# 06_MIMXRT1170_PART2.net
KiCad netlist of a schematic drawn in Altium Designer
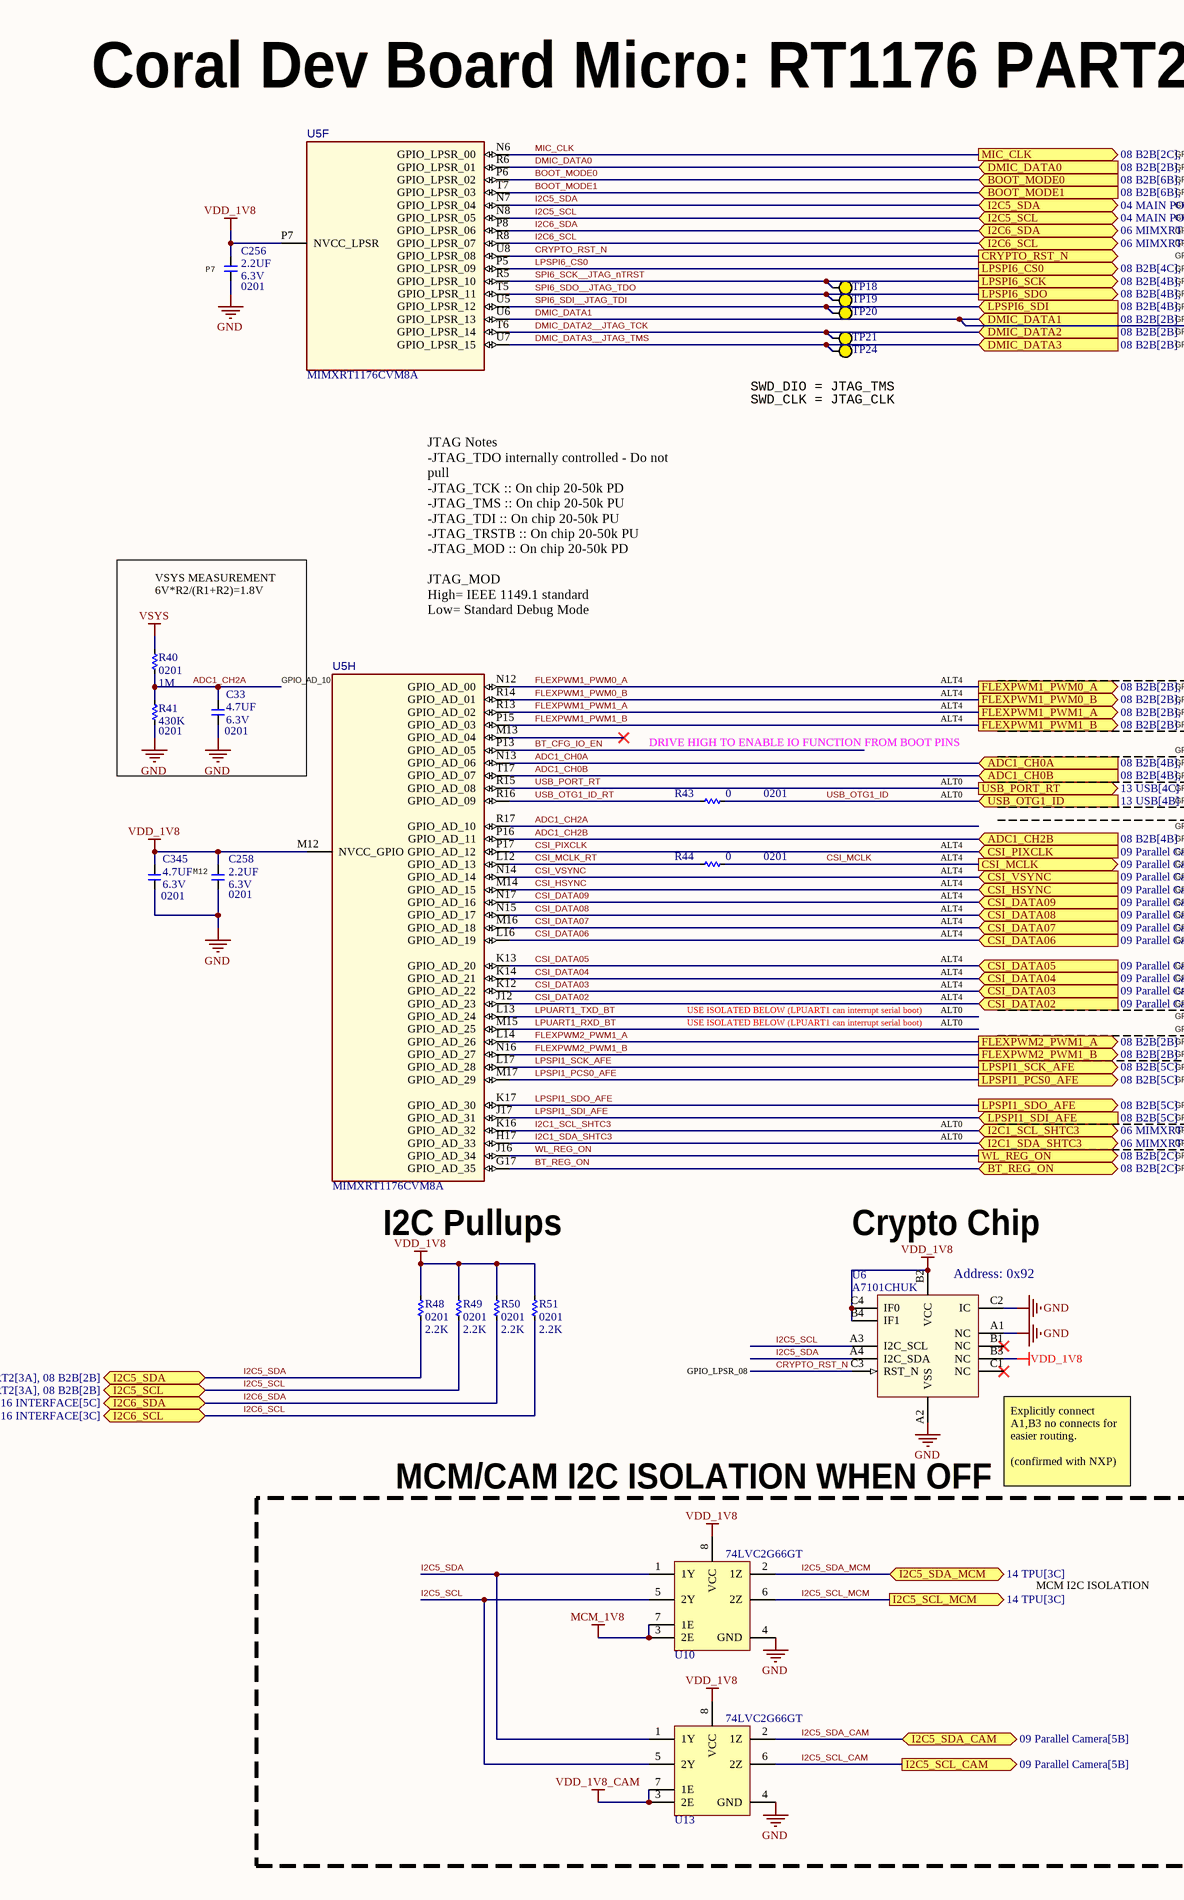
[diagram p0: 06 MIMXRT1170 PART2.SchDoc, left]
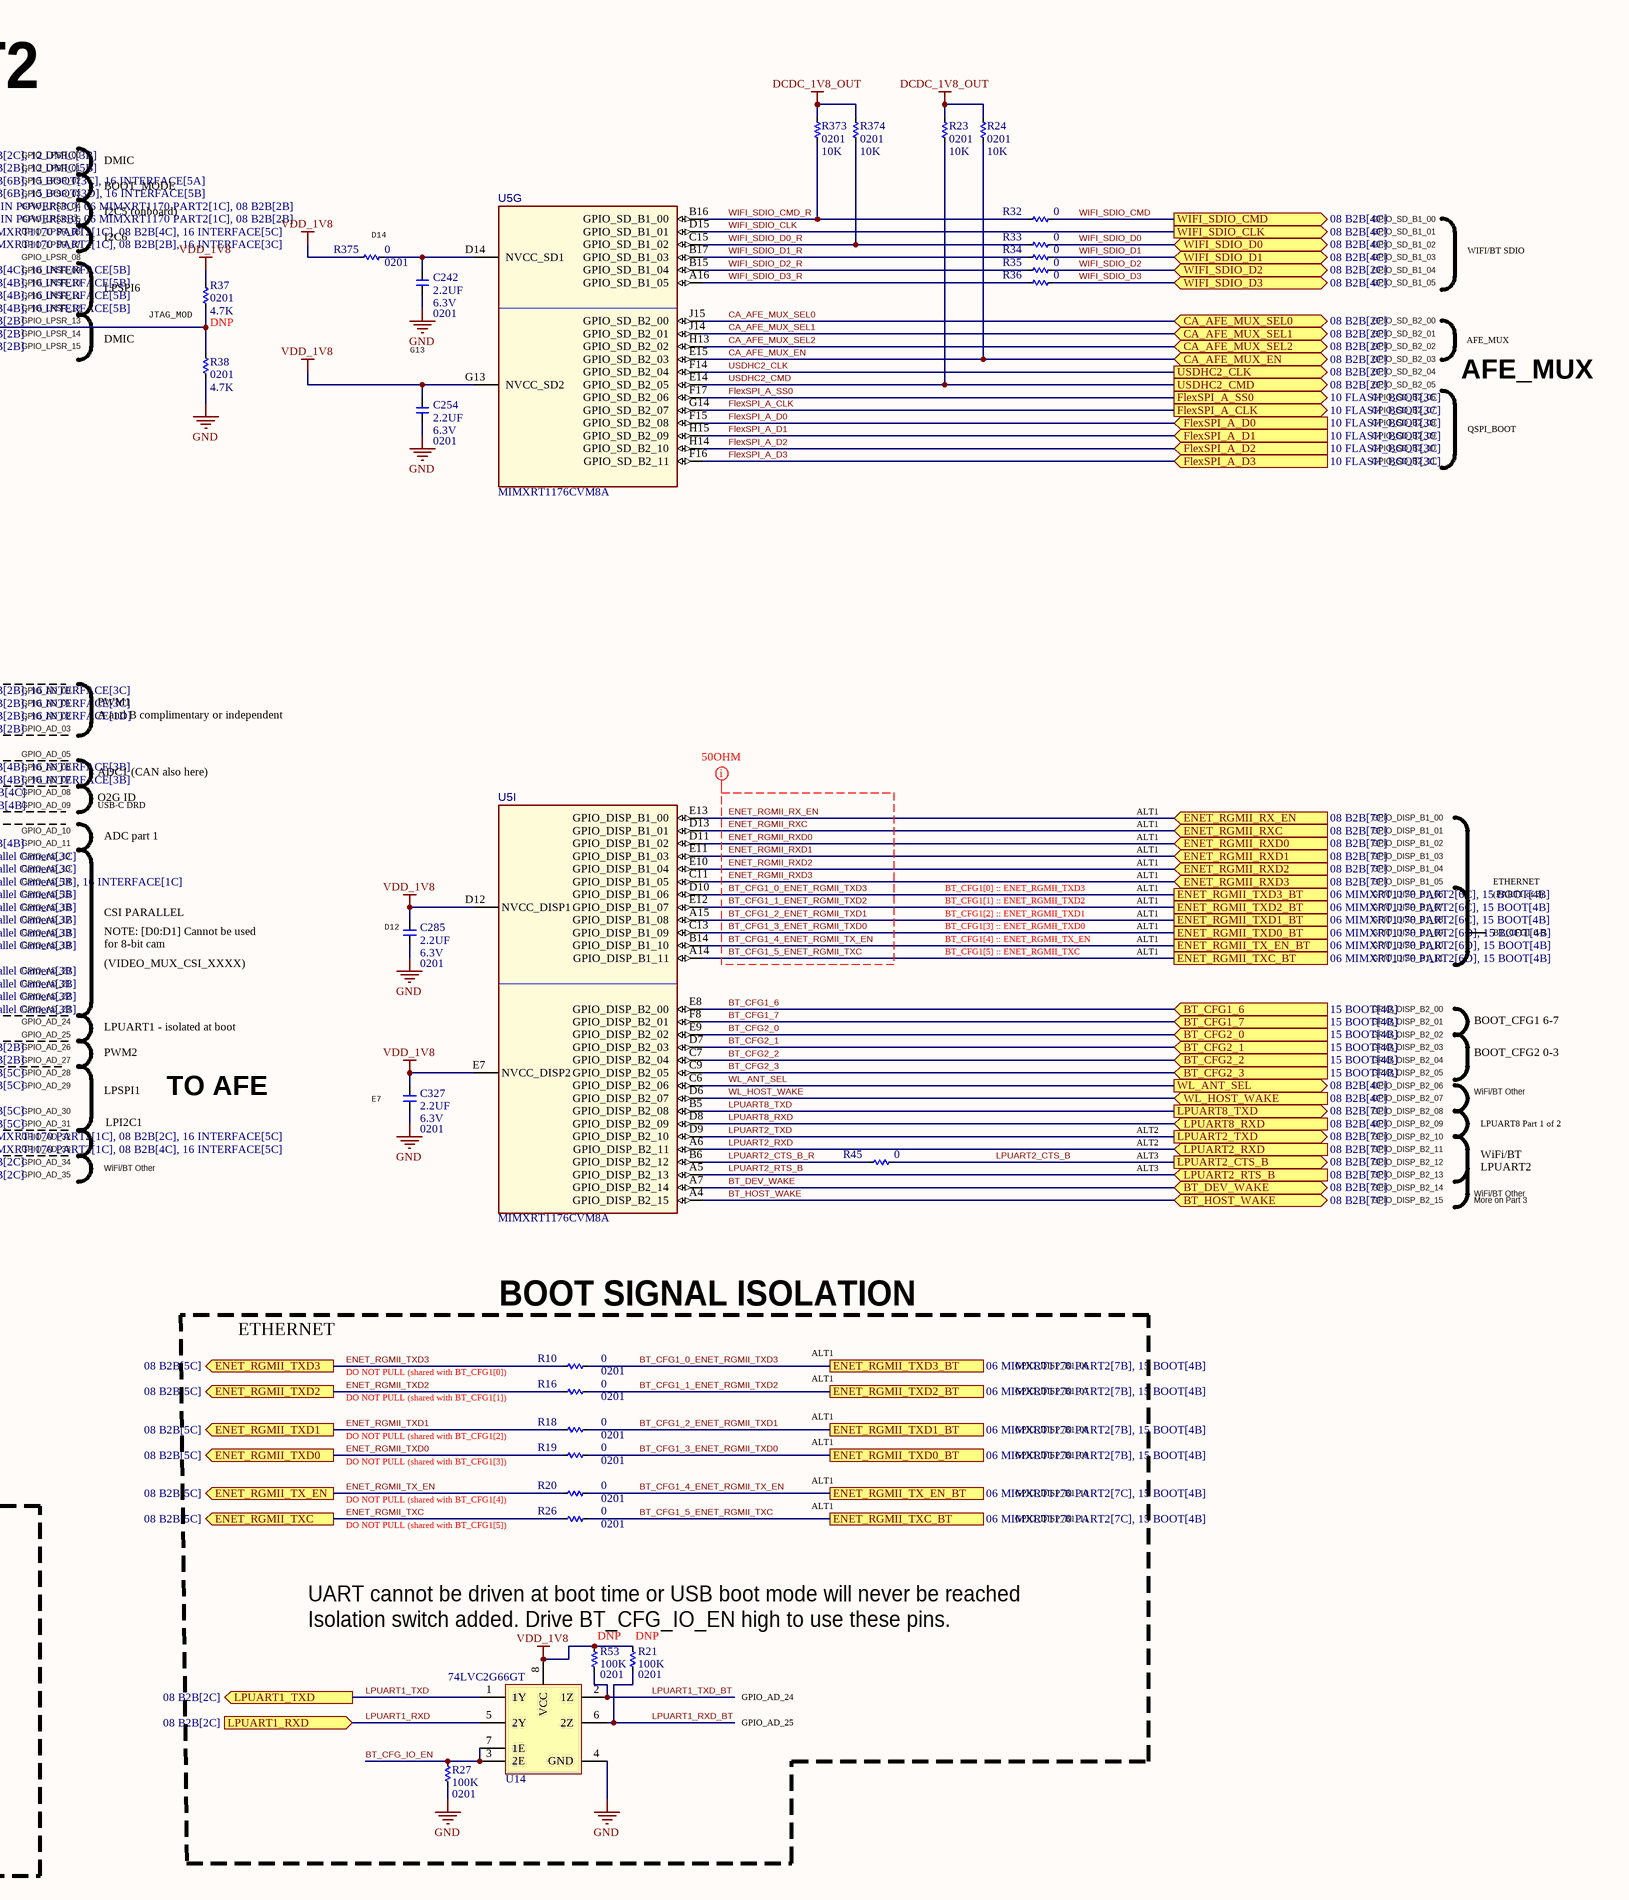
[diagram p1: 06 MIMXRT1170 PART2.SchDoc, right]

(export (version "E")
  (design (tool "Eeschema 10.0.6"))
  (components
    (comp (ref "C33")
      (value "4.7UF")
      (footprint "C0201Y")
      (description "CAP, CER, X5R, 4.7uF, 20%, 6.3V, 0201")
      (fields
        (field (name "MFG") "MURATA")
        (field (name "PACKAGE") "0201")
        (field (name "VOLTAGE") "6.3V")
        (field (name "TOLERANCE") "20%")
      )
      (libsource (lib "AltiumReleaseLibDB") (part "__Template_Cap"))
    )
    (comp (ref "C242")
      (value "2.2UF")
      (footprint "C0201_H0.39MM")
      (description "CAP, CER, X5R, 2.2uF, 20%, 6.3V, 0201, 0.39mm")
      (fields
        (field (name "MFG") "YAGEO")
        (field (name "PACKAGE") "0201")
        (field (name "VOLTAGE") "6.3V")
        (field (name "TOLERANCE") "20%")
      )
      (libsource (lib "AltiumReleaseLibDB") (part "__Template_Cap"))
    )
    (comp (ref "C254")
      (value "2.2UF")
      (footprint "C0201_H0.39MM")
      (description "CAP, CER, X5R, 2.2uF, 20%, 6.3V, 0201, 0.39mm")
      (fields
        (field (name "MFG") "YAGEO")
        (field (name "PACKAGE") "0201")
        (field (name "VOLTAGE") "6.3V")
        (field (name "TOLERANCE") "20%")
      )
      (libsource (lib "AltiumReleaseLibDB") (part "__Template_Cap"))
    )
    (comp (ref "C256")
      (value "2.2UF")
      (footprint "C0201_H0.39MM")
      (description "CAP, CER, X5R, 2.2uF, 20%, 6.3V, 0201, 0.39mm")
      (fields
        (field (name "MFG") "YAGEO")
        (field (name "PACKAGE") "0201")
        (field (name "VOLTAGE") "6.3V")
        (field (name "TOLERANCE") "20%")
      )
      (libsource (lib "AltiumReleaseLibDB") (part "__Template_Cap"))
    )
    (comp (ref "C258")
      (value "2.2UF")
      (footprint "C0201_H0.39MM")
      (description "CAP, CER, X5R, 2.2uF, 20%, 6.3V, 0201, 0.39mm")
      (fields
        (field (name "MFG") "YAGEO")
        (field (name "PACKAGE") "0201")
        (field (name "VOLTAGE") "6.3V")
        (field (name "TOLERANCE") "20%")
      )
      (libsource (lib "AltiumReleaseLibDB") (part "__Template_Cap"))
    )
    (comp (ref "C285")
      (value "2.2UF")
      (footprint "C0201_H0.39MM")
      (description "CAP, CER, X5R, 2.2uF, 20%, 6.3V, 0201, 0.39mm")
      (fields
        (field (name "MFG") "YAGEO")
        (field (name "PACKAGE") "0201")
        (field (name "VOLTAGE") "6.3V")
        (field (name "TOLERANCE") "20%")
      )
      (libsource (lib "AltiumReleaseLibDB") (part "__Template_Cap"))
    )
    (comp (ref "C327")
      (value "2.2UF")
      (footprint "C0201_H0.39MM")
      (description "CAP, CER, X5R, 2.2uF, 20%, 6.3V, 0201, 0.39mm")
      (fields
        (field (name "MFG") "YAGEO")
        (field (name "PACKAGE") "0201")
        (field (name "VOLTAGE") "6.3V")
        (field (name "TOLERANCE") "20%")
      )
      (libsource (lib "AltiumReleaseLibDB") (part "__Template_Cap"))
    )
    (comp (ref "C345")
      (value "4.7UF")
      (footprint "C0201Y")
      (description "CAP, CER, X5R, 4.7uF, 20%, 6.3V, 0201")
      (fields
        (field (name "MFG") "MURATA")
        (field (name "PACKAGE") "0201")
        (field (name "VOLTAGE") "6.3V")
        (field (name "TOLERANCE") "20%")
      )
      (libsource (lib "AltiumReleaseLibDB") (part "__Template_Cap"))
    )
    (comp (ref "R10")
      (value "0")
      (footprint "R0201")
      (description "RES, 0.0, 1/20W, 0201")
      (fields (field (name "MFG") "PANASONIC") (field (name "PACKAGE") "0201") (field (name "POWER") "1/20W"))
      (libsource (lib "AltiumReleaseLibDB") (part "__Template_Resistor"))
    )
    (comp (ref "R16")
      (value "0")
      (footprint "R0201")
      (description "RES, 0.0, 1/20W, 0201")
      (fields (field (name "MFG") "PANASONIC") (field (name "PACKAGE") "0201") (field (name "POWER") "1/20W"))
      (libsource (lib "AltiumReleaseLibDB") (part "__Template_Resistor"))
    )
    (comp (ref "R18")
      (value "0")
      (footprint "R0201")
      (description "RES, 0.0, 1/20W, 0201")
      (fields (field (name "MFG") "PANASONIC") (field (name "PACKAGE") "0201") (field (name "POWER") "1/20W"))
      (libsource (lib "AltiumReleaseLibDB") (part "__Template_Resistor"))
    )
    (comp (ref "R19")
      (value "0")
      (footprint "R0201")
      (description "RES, 0.0, 1/20W, 0201")
      (fields (field (name "MFG") "PANASONIC") (field (name "PACKAGE") "0201") (field (name "POWER") "1/20W"))
      (libsource (lib "AltiumReleaseLibDB") (part "__Template_Resistor"))
    )
    (comp (ref "R20")
      (value "0")
      (footprint "R0201")
      (description "RES, 0.0, 1/20W, 0201")
      (fields (field (name "MFG") "PANASONIC") (field (name "PACKAGE") "0201") (field (name "POWER") "1/20W"))
      (libsource (lib "AltiumReleaseLibDB") (part "__Template_Resistor"))
    )
    (comp (ref "R21")
      (value "100K")
      (footprint "R0201")
      (description "RES, 100K, 1%, 1/20W, 0201")
      (fields
        (field (name "MFG") "PANASONIC")
        (field (name "PACKAGE") "0201")
        (field (name "POWER") "1/20W")
        (field (name "DNP") "DNP")
      )
      (libsource (lib "AltiumReleaseLibDB") (part "__Template_Resistor"))
    )
    (comp (ref "R23")
      (value "10K")
      (footprint "R0201")
      (description "RES, 10K, 1%, 1/20W, 0201")
      (fields (field (name "MFG") "YAGEO") (field (name "PACKAGE") "0201") (field (name "POWER") "1/20W"))
      (libsource (lib "AltiumReleaseLibDB") (part "__Template_Resistor"))
    )
    (comp (ref "R24")
      (value "10K")
      (footprint "R0201")
      (description "RES, 10K, 1%, 1/20W, 0201")
      (fields (field (name "MFG") "YAGEO") (field (name "PACKAGE") "0201") (field (name "POWER") "1/20W"))
      (libsource (lib "AltiumReleaseLibDB") (part "__Template_Resistor"))
    )
    (comp (ref "R26")
      (value "0")
      (footprint "R0201")
      (description "RES, 0.0, 1/20W, 0201")
      (fields (field (name "MFG") "PANASONIC") (field (name "PACKAGE") "0201") (field (name "POWER") "1/20W"))
      (libsource (lib "AltiumReleaseLibDB") (part "__Template_Resistor"))
    )
    (comp (ref "R27")
      (value "100K")
      (footprint "R0201")
      (description "RES, 100K, 1%, 1/20W, 0201")
      (fields (field (name "MFG") "PANASONIC") (field (name "PACKAGE") "0201") (field (name "POWER") "1/20W"))
      (libsource (lib "AltiumReleaseLibDB") (part "__Template_Resistor"))
    )
    (comp (ref "R32")
      (value "0")
      (footprint "R0201")
      (description "RES, 0.0, 1/20W, 0201")
      (fields (field (name "MFG") "PANASONIC") (field (name "POWER") "1/20W"))
      (libsource (lib "AltiumReleaseLibDB") (part "__Template_Resistor"))
    )
    (comp (ref "R33")
      (value "0")
      (footprint "R0201")
      (description "RES, 0.0, 1/20W, 0201")
      (fields (field (name "MFG") "PANASONIC") (field (name "POWER") "1/20W"))
      (libsource (lib "AltiumReleaseLibDB") (part "__Template_Resistor"))
    )
    (comp (ref "R34")
      (value "0")
      (footprint "R0201")
      (description "RES, 0.0, 1/20W, 0201")
      (fields (field (name "MFG") "PANASONIC") (field (name "POWER") "1/20W"))
      (libsource (lib "AltiumReleaseLibDB") (part "__Template_Resistor"))
    )
    (comp (ref "R35")
      (value "0")
      (footprint "R0201")
      (description "RES, 0.0, 1/20W, 0201")
      (fields (field (name "MFG") "PANASONIC") (field (name "POWER") "1/20W"))
      (libsource (lib "AltiumReleaseLibDB") (part "__Template_Resistor"))
    )
    (comp (ref "R36")
      (value "0")
      (footprint "R0201")
      (description "RES, 0.0, 1/20W, 0201")
      (fields (field (name "MFG") "PANASONIC") (field (name "POWER") "1/20W"))
      (libsource (lib "AltiumReleaseLibDB") (part "__Template_Resistor"))
    )
    (comp (ref "R37")
      (value "4.7K")
      (footprint "R0201")
      (description "RES, 4.7K, 5%, 1/20W, 0201")
      (fields
        (field (name "MFG") "YAGEO")
        (field (name "PACKAGE") "0201")
        (field (name "POWER") "1/20W")
        (field (name "DNP") "DNP")
      )
      (libsource (lib "AltiumReleaseLibDB") (part "__Template_Resistor"))
    )
    (comp (ref "R38")
      (value "4.7K")
      (footprint "R0201")
      (description "RES, 4.7K, 5%, 1/20W, 0201")
      (fields (field (name "MFG") "YAGEO") (field (name "PACKAGE") "0201") (field (name "POWER") "1/20W"))
      (libsource (lib "AltiumReleaseLibDB") (part "__Template_Resistor"))
    )
    (comp (ref "R40")
      (value "1M")
      (footprint "R0201")
      (description "RES, 1M, 1%, 1/20W, 0201")
      (fields (field (name "MFG") "PANASONIC") (field (name "PACKAGE") "0201") (field (name "POWER") "1/20W"))
      (libsource (lib "AltiumReleaseLibDB") (part "__Template_Resistor"))
    )
    (comp (ref "R41")
      (value "430K")
      (footprint "R0201")
      (description "Resistor, 430K Ohms, 0201, 0.05W, ±1%")
      (fields (field (name "MFG") "PANASONIC") (field (name "PACKAGE") "0201") (field (name "POWER") "1/20W"))
      (libsource (lib "AltiumReleaseLibDB") (part "__Template_Resistor"))
    )
    (comp (ref "R43")
      (value "0")
      (footprint "R0201")
      (description "RES, 0.0, 1/20W, 0201")
      (fields (field (name "MFG") "PANASONIC") (field (name "PACKAGE") "0201") (field (name "POWER") "1/20W"))
      (libsource (lib "AltiumReleaseLibDB") (part "__Template_Resistor"))
    )
    (comp (ref "R44")
      (value "0")
      (footprint "R0201")
      (description "RES, 0.0, 1/20W, 0201")
      (fields (field (name "MFG") "PANASONIC") (field (name "PACKAGE") "0201") (field (name "POWER") "1/20W"))
      (libsource (lib "AltiumReleaseLibDB") (part "__Template_Resistor"))
    )
    (comp (ref "R45")
      (value "0")
      (footprint "R0201")
      (description "RES, 0.0, 1/20W, 0201")
      (fields (field (name "MFG") "PANASONIC") (field (name "POWER") "1/20W"))
      (libsource (lib "AltiumReleaseLibDB") (part "__Template_Resistor"))
    )
    (comp (ref "R48")
      (value "2.2K")
      (footprint "R0201")
      (description "RES, 2.2K, 5%, 1/20W, 0201")
      (fields (field (name "MFG") "YAGEO") (field (name "PACKAGE") "0201") (field (name "POWER") "1/20W"))
      (libsource (lib "AltiumReleaseLibDB") (part "__Template_Resistor"))
    )
    (comp (ref "R49")
      (value "2.2K")
      (footprint "R0201")
      (description "RES, 2.2K, 5%, 1/20W, 0201")
      (fields (field (name "MFG") "YAGEO") (field (name "PACKAGE") "0201") (field (name "POWER") "1/20W"))
      (libsource (lib "AltiumReleaseLibDB") (part "__Template_Resistor"))
    )
    (comp (ref "R50")
      (value "2.2K")
      (footprint "R0201")
      (description "RES, 2.2K, 5%, 1/20W, 0201")
      (fields (field (name "MFG") "YAGEO") (field (name "PACKAGE") "0201") (field (name "POWER") "1/20W"))
      (libsource (lib "AltiumReleaseLibDB") (part "__Template_Resistor"))
    )
    (comp (ref "R51")
      (value "2.2K")
      (footprint "R0201")
      (description "RES, 2.2K, 5%, 1/20W, 0201")
      (fields (field (name "MFG") "YAGEO") (field (name "PACKAGE") "0201") (field (name "POWER") "1/20W"))
      (libsource (lib "AltiumReleaseLibDB") (part "__Template_Resistor"))
    )
    (comp (ref "R53")
      (value "100K")
      (footprint "R0201")
      (description "RES, 100K, 1%, 1/20W, 0201")
      (fields
        (field (name "MFG") "PANASONIC")
        (field (name "PACKAGE") "0201")
        (field (name "POWER") "1/20W")
        (field (name "DNP") "DNP")
      )
      (libsource (lib "AltiumReleaseLibDB") (part "__Template_Resistor"))
    )
    (comp (ref "R373")
      (value "10K")
      (footprint "R0201")
      (description "RES, 10K, 1%, 1/20W, 0201")
      (fields (field (name "MFG") "YAGEO") (field (name "PACKAGE") "0201") (field (name "POWER") "1/20W"))
      (libsource (lib "AltiumReleaseLibDB") (part "__Template_Resistor"))
    )
    (comp (ref "R374")
      (value "10K")
      (footprint "R0201")
      (description "RES, 10K, 1%, 1/20W, 0201")
      (fields (field (name "MFG") "YAGEO") (field (name "PACKAGE") "0201") (field (name "POWER") "1/20W"))
      (libsource (lib "AltiumReleaseLibDB") (part "__Template_Resistor"))
    )
    (comp (ref "R375")
      (value "0")
      (footprint "R0201")
      (description "RES, 0.0, 1/20W, 0201")
      (fields (field (name "MFG") "PANASONIC") (field (name "PACKAGE") "0201") (field (name "POWER") "1/20W"))
      (libsource (lib "AltiumReleaseLibDB") (part "__Template_Resistor"))
    )
    (comp (ref "TP18")
      (value "TESTPAD_30MIL")
      (footprint "TESTPAD_SMT_30MIL")
      (description "TESTPAD_SMT_30MIL")
      (fields (field (name "MFG") "_PCB Feature"))
      (libsource (lib "AltiumReleaseLibDB") (part "TESTPAD_30MIL"))
    )
    (comp (ref "TP19")
      (value "TESTPAD_30MIL")
      (footprint "TESTPAD_SMT_30MIL")
      (description "TESTPAD_SMT_30MIL")
      (fields (field (name "MFG") "_PCB Feature"))
      (libsource (lib "AltiumReleaseLibDB") (part "TESTPAD_30MIL"))
    )
    (comp (ref "TP20")
      (value "TESTPAD_30MIL")
      (footprint "TESTPAD_SMT_30MIL")
      (description "TESTPAD_SMT_30MIL")
      (fields (field (name "MFG") "_PCB Feature"))
      (libsource (lib "AltiumReleaseLibDB") (part "TESTPAD_30MIL"))
    )
    (comp (ref "TP21")
      (value "TESTPAD_30MIL")
      (footprint "TESTPAD_SMT_30MIL")
      (description "TESTPAD_SMT_30MIL")
      (fields (field (name "MFG") "_PCB Feature"))
      (libsource (lib "AltiumReleaseLibDB") (part "TESTPAD_30MIL"))
    )
    (comp (ref "TP24")
      (value "TESTPAD_30MIL")
      (footprint "TESTPAD_SMT_30MIL")
      (description "TESTPAD_SMT_30MIL")
      (fields (field (name "MFG") "_PCB Feature"))
      (libsource (lib "AltiumReleaseLibDB") (part "TESTPAD_30MIL"))
    )
    (comp (ref "U5")
      (value "MCU_MIMXRT1176CVM8A")
      (footprint "BGA289C80P17X17_1400X14000X152")
      (description "IC, PROCESSOR, MIMXRT1176CV, ARM CORTEX-M4/M7, 2MB RAM, SDRAM, WLAN, BGA-289")
      (fields (field (name "MFG") "NXP Semiconductors") (field (name "MFG P/N") "MIMXRT1176CVM8A"))
      (libsource (lib "AltiumReleaseLibDB") (part "MCU_MIMXRT1176CVM8A"))
    )
    (comp (ref "U6")
      (value "SECUR_AUTH_A7101CHUK")
      (footprint "BGA12C50+3X4_206X202X65")
      (description "IC, MICRO CONTROLLER, A7101, MX51, SECURITY, TEMP, AUTHENTICATION, I2C, WLCSP-12")
      (fields (field (name "MFG") "NXP USA Inc.") (field (name "MFG P/N") "A7101CHUK"))
      (libsource (lib "AltiumReleaseLibDB") (part "SECUR_AUTH_A7101CHUK"))
    )
    (comp (ref "U10")
      (value "74LVC2G66GT")
      (footprint "SON8_0P5_1L95x1W")
      (description "SPST 2x, 1.65V ~ 5.5V, XSON8, 500MHz at 50Ohm")
      (libsource (lib "Valiant_P0") (part "74LVC2G66GT"))
    )
    (comp (ref "U13")
      (value "74LVC2G66GT")
      (footprint "SON8_0P5_1L95x1W")
      (description "SPST 2x, 1.65V ~ 5.5V, XSON8, 500MHz at 50Ohm")
      (libsource (lib "Valiant_P0") (part "74LVC2G66GT"))
    )
    (comp (ref "U14")
      (value "74LVC2G66GT")
      (footprint "SON8_0P5_1L95x1W")
      (description "SPST 2x, 1.65V ~ 5.5V, XSON8, 500MHz at 50Ohm")
      (libsource (lib "Valiant_P0") (part "74LVC2G66GT"))
    )
  )
  (nets
    (net (code "1") (name "/ADC1_CH0A") (class "Default")
      (node (ref "U5") (pin "N13") (pinfunction "GPIO_AD_06_N13") (pintype "bidirectional"))
    )
    (net (code "2") (name "/ADC1_CH0B") (class "Default")
      (node (ref "U5") (pin "T17") (pinfunction "GPIO_AD_07_T17") (pintype "bidirectional"))
    )
    (net (code "3") (name "/ADC1_CH2A") (class "Default")
      (node (ref "C33") (pin "1") (pintype "passive"))
      (node (ref "R40") (pin "1") (pintype "passive"))
      (node (ref "R41") (pin "2") (pintype "passive"))
      (node (ref "U5") (pin "R17") (pinfunction "GPIO_AD_10_R17") (pintype "bidirectional"))
    )
    (net (code "4") (name "/ADC1_CH2B") (class "Default")
      (node (ref "U5") (pin "P16") (pinfunction "GPIO_AD_11_P16") (pintype "bidirectional"))
    )
    (net (code "5") (name "/BOOT_MODE0") (class "Default")
      (node (ref "U5") (pin "P6") (pinfunction "GPIO_LPSR_02_P6") (pintype "bidirectional"))
    )
    (net (code "6") (name "/BOOT_MODE1") (class "Default")
      (node (ref "U5") (pin "T7") (pinfunction "GPIO_LPSR_03_T7") (pintype "bidirectional"))
    )
    (net (code "7") (name "/BT_CFG1_0_ENET_RGMII_TXD3") (class "Default")
      (node (ref "R10") (pin "2") (pintype "passive"))
      (node (ref "U5") (pin "D10") (pinfunction "GPIO_DISP_B1_06_D10") (pintype "bidirectional"))
    )
    (net (code "8") (name "/BT_CFG1_1_ENET_RGMII_TXD2") (class "Default")
      (node (ref "R16") (pin "2") (pintype "passive"))
      (node (ref "U5") (pin "E12") (pinfunction "GPIO_DISP_B1_07_E12") (pintype "bidirectional"))
    )
    (net (code "9") (name "/BT_CFG1_2_ENET_RGMII_TXD1") (class "Default")
      (node (ref "R18") (pin "2") (pintype "passive"))
      (node (ref "U5") (pin "A15") (pinfunction "GPIO_DISP_B1_08_A15") (pintype "bidirectional"))
    )
    (net (code "10") (name "/BT_CFG1_3_ENET_RGMII_TXD0") (class "Default")
      (node (ref "R19") (pin "2") (pintype "passive"))
      (node (ref "U5") (pin "C13") (pinfunction "GPIO_DISP_B1_09_C13") (pintype "bidirectional"))
    )
    (net (code "11") (name "/BT_CFG1_4_ENET_RGMII_TX_EN") (class "Default")
      (node (ref "R20") (pin "2") (pintype "passive"))
      (node (ref "U5") (pin "B14") (pinfunction "GPIO_DISP_B1_10_B14") (pintype "bidirectional"))
    )
    (net (code "12") (name "/BT_CFG1_5_ENET_RGMII_TXC") (class "Default")
      (node (ref "R26") (pin "2") (pintype "passive"))
      (node (ref "U5") (pin "A14") (pinfunction "GPIO_DISP_B1_11_A14") (pintype "bidirectional"))
    )
    (net (code "13") (name "/BT_CFG1_6") (class "Default")
      (node (ref "U5") (pin "E8") (pinfunction "GPIO_DISP_B2_00_E8") (pintype "bidirectional"))
    )
    (net (code "14") (name "/BT_CFG1_7") (class "Default")
      (node (ref "U5") (pin "F8") (pinfunction "GPIO_DISP_B2_01_F8") (pintype "bidirectional"))
    )
    (net (code "15") (name "/BT_CFG2_0") (class "Default")
      (node (ref "U5") (pin "E9") (pinfunction "GPIO_DISP_B2_02_E9") (pintype "bidirectional"))
    )
    (net (code "16") (name "/BT_CFG2_1") (class "Default")
      (node (ref "U5") (pin "D7") (pinfunction "GPIO_DISP_B2_03_D7") (pintype "bidirectional"))
    )
    (net (code "17") (name "/BT_CFG2_2") (class "Default")
      (node (ref "U5") (pin "C7") (pinfunction "GPIO_DISP_B2_04_C7") (pintype "bidirectional"))
    )
    (net (code "18") (name "/BT_CFG2_3") (class "Default")
      (node (ref "U5") (pin "C9") (pinfunction "GPIO_DISP_B2_05_C9") (pintype "bidirectional"))
    )
    (net (code "19") (name "/BT_CFG_IO_EN") (class "Default")
      (node (ref "R27") (pin "2") (pintype "passive"))
      (node (ref "U14") (pin "3") (pinfunction "2E_3") (pintype "passive"))
      (node (ref "U14") (pin "7") (pinfunction "1E_7") (pintype "passive"))
      (node (ref "U5") (pin "P13") (pinfunction "GPIO_AD_05_P13") (pintype "bidirectional"))
    )
    (net (code "20") (name "/BT_DEV_WAKE") (class "Default")
      (node (ref "U5") (pin "A7") (pinfunction "GPIO_DISP_B2_14_A7") (pintype "bidirectional"))
    )
    (net (code "21") (name "/BT_HOST_WAKE") (class "Default")
      (node (ref "U5") (pin "A4") (pinfunction "GPIO_DISP_B2_15_A4") (pintype "bidirectional"))
    )
    (net (code "22") (name "/BT_REG_ON") (class "Default")
      (node (ref "U5") (pin "G17") (pinfunction "GPIO_AD_35_G17") (pintype "bidirectional"))
    )
    (net (code "23") (name "/CA_AFE_MUX_EN") (class "Default")
      (node (ref "R24") (pin "1") (pintype "passive"))
      (node (ref "U5") (pin "E15") (pinfunction "GPIO_SD_B2_03_E15") (pintype "bidirectional"))
    )
    (net (code "24") (name "/CA_AFE_MUX_SEL0") (class "Default")
      (node (ref "U5") (pin "J15") (pinfunction "GPIO_SD_B2_00_J15") (pintype "bidirectional"))
    )
    (net (code "25") (name "/CA_AFE_MUX_SEL1") (class "Default")
      (node (ref "U5") (pin "J14") (pinfunction "GPIO_SD_B2_01_J14") (pintype "bidirectional"))
    )
    (net (code "26") (name "/CA_AFE_MUX_SEL2") (class "Default")
      (node (ref "U5") (pin "H13") (pinfunction "GPIO_SD_B2_02_H13") (pintype "bidirectional"))
    )
    (net (code "27") (name "/CRYPTO_RST_N") (class "Default")
      (node (ref "U5") (pin "U8") (pinfunction "GPIO_LPSR_08_U8") (pintype "bidirectional"))
      (node (ref "U6") (pin "C3") (pinfunction "RST_N_C3") (pintype "input"))
    )
    (net (code "28") (name "/CSI_DATA02") (class "Default")
      (node (ref "U5") (pin "J12") (pinfunction "GPIO_AD_23_J12") (pintype "bidirectional"))
    )
    (net (code "29") (name "/CSI_DATA03") (class "Default")
      (node (ref "U5") (pin "K12") (pinfunction "GPIO_AD_22_K12") (pintype "bidirectional"))
    )
    (net (code "30") (name "/CSI_DATA04") (class "Default")
      (node (ref "U5") (pin "K14") (pinfunction "GPIO_AD_21_K14") (pintype "bidirectional"))
    )
    (net (code "31") (name "/CSI_DATA05") (class "Default")
      (node (ref "U5") (pin "K13") (pinfunction "GPIO_AD_20_K13") (pintype "bidirectional"))
    )
    (net (code "32") (name "/CSI_DATA06") (class "Default")
      (node (ref "U5") (pin "L16") (pinfunction "GPIO_AD_19_L16") (pintype "bidirectional"))
    )
    (net (code "33") (name "/CSI_DATA07") (class "Default")
      (node (ref "U5") (pin "M16") (pinfunction "GPIO_AD_18_M16") (pintype "bidirectional"))
    )
    (net (code "34") (name "/CSI_DATA08") (class "Default")
      (node (ref "U5") (pin "N15") (pinfunction "GPIO_AD_17_N15") (pintype "bidirectional"))
    )
    (net (code "35") (name "/CSI_DATA09") (class "Default")
      (node (ref "U5") (pin "N17") (pinfunction "GPIO_AD_16_N17") (pintype "bidirectional"))
    )
    (net (code "36") (name "/CSI_HSYNC") (class "Default")
      (node (ref "U5") (pin "M14") (pinfunction "GPIO_AD_15_M14") (pintype "bidirectional"))
    )
    (net (code "37") (name "/CSI_MCLK") (class "Default") (node (ref "R44") (pin "2") (pintype "passive")))
    (net (code "38") (name "/CSI_MCLK_RT") (class "Default")
      (node (ref "R44") (pin "1") (pintype "passive"))
      (node (ref "U5") (pin "L12") (pinfunction "GPIO_AD_13_L12") (pintype "bidirectional"))
    )
    (net (code "39") (name "/CSI_PIXCLK") (class "Default")
      (node (ref "U5") (pin "P17") (pinfunction "GPIO_AD_12_P17") (pintype "bidirectional"))
    )
    (net (code "40") (name "/CSI_VSYNC") (class "Default")
      (node (ref "U5") (pin "N14") (pinfunction "GPIO_AD_14_N14") (pintype "bidirectional"))
    )
    (net (code "41") (name "/DMIC_DATA0") (class "Default")
      (node (ref "U5") (pin "R6") (pinfunction "GPIO_LPSR_01_R6") (pintype "bidirectional"))
    )
    (net (code "42") (name "/DMIC_DATA1") (class "Default")
      (node (ref "R37") (pin "1") (pintype "passive"))
      (node (ref "R38") (pin "2") (pintype "passive"))
      (node (ref "U5") (pin "U6") (pinfunction "GPIO_LPSR_13_U6") (pintype "bidirectional"))
    )
    (net (code "43") (name "/DMIC_DATA2__JTAG_TCK") (class "Default")
      (node (ref "TP21") (pin "1") (pintype "passive"))
      (node (ref "U5") (pin "T6") (pinfunction "GPIO_LPSR_14_T6") (pintype "bidirectional"))
    )
    (net (code "44") (name "/DMIC_DATA3__JTAG_TMS") (class "Default")
      (node (ref "TP24") (pin "1") (pintype "passive"))
      (node (ref "U5") (pin "U7") (pinfunction "GPIO_LPSR_15_U7") (pintype "bidirectional"))
    )
    (net (code "45") (name "/ENET_RGMII_RXC") (class "Default")
      (node (ref "U5") (pin "D13") (pinfunction "GPIO_DISP_B1_01_D13") (pintype "bidirectional"))
    )
    (net (code "46") (name "/ENET_RGMII_RXD0") (class "Default")
      (node (ref "U5") (pin "D11") (pinfunction "GPIO_DISP_B1_02_D11") (pintype "bidirectional"))
    )
    (net (code "47") (name "/ENET_RGMII_RXD1") (class "Default")
      (node (ref "U5") (pin "E11") (pinfunction "GPIO_DISP_B1_03_E11") (pintype "bidirectional"))
    )
    (net (code "48") (name "/ENET_RGMII_RXD2") (class "Default")
      (node (ref "U5") (pin "E10") (pinfunction "GPIO_DISP_B1_04_E10") (pintype "bidirectional"))
    )
    (net (code "49") (name "/ENET_RGMII_RXD3") (class "Default")
      (node (ref "U5") (pin "C11") (pinfunction "GPIO_DISP_B1_05_C11") (pintype "bidirectional"))
    )
    (net (code "50") (name "/ENET_RGMII_RX_EN") (class "Default")
      (node (ref "U5") (pin "E13") (pinfunction "GPIO_DISP_B1_00_E13") (pintype "bidirectional"))
    )
    (net (code "51") (name "/ENET_RGMII_TXC") (class "Default")
      (node (ref "R26") (pin "1") (pintype "passive"))
    )
    (net (code "52") (name "/ENET_RGMII_TXD0") (class "Default")
      (node (ref "R19") (pin "1") (pintype "passive"))
    )
    (net (code "53") (name "/ENET_RGMII_TXD1") (class "Default")
      (node (ref "R18") (pin "1") (pintype "passive"))
    )
    (net (code "54") (name "/ENET_RGMII_TXD2") (class "Default")
      (node (ref "R16") (pin "1") (pintype "passive"))
    )
    (net (code "55") (name "/ENET_RGMII_TXD3") (class "Default")
      (node (ref "R10") (pin "1") (pintype "passive"))
    )
    (net (code "56") (name "/ENET_RGMII_TX_EN") (class "Default")
      (node (ref "R20") (pin "1") (pintype "passive"))
    )
    (net (code "57") (name "/FLEXPWM1_PWM0_A") (class "Default")
      (node (ref "U5") (pin "N12") (pinfunction "GPIO_AD_00_N12") (pintype "bidirectional"))
    )
    (net (code "58") (name "/FLEXPWM1_PWM0_B") (class "Default")
      (node (ref "U5") (pin "R14") (pinfunction "GPIO_AD_01_R14") (pintype "bidirectional"))
    )
    (net (code "59") (name "/FLEXPWM1_PWM1_A") (class "Default")
      (node (ref "U5") (pin "R13") (pinfunction "GPIO_AD_02_R13") (pintype "bidirectional"))
    )
    (net (code "60") (name "/FLEXPWM1_PWM1_B") (class "Default")
      (node (ref "U5") (pin "P15") (pinfunction "GPIO_AD_03_P15") (pintype "bidirectional"))
    )
    (net (code "61") (name "/FLEXPWM2_PWM1_A") (class "Default")
      (node (ref "U5") (pin "L14") (pinfunction "GPIO_AD_26_L14") (pintype "bidirectional"))
    )
    (net (code "62") (name "/FLEXPWM2_PWM1_B") (class "Default")
      (node (ref "U5") (pin "N16") (pinfunction "GPIO_AD_27_N16") (pintype "bidirectional"))
    )
    (net (code "63") (name "/FlexSPI_A_CLK") (class "Default")
      (node (ref "U5") (pin "G14") (pinfunction "GPIO_SD_B2_07_G14") (pintype "bidirectional"))
    )
    (net (code "64") (name "/FlexSPI_A_D0") (class "Default")
      (node (ref "U5") (pin "F15") (pinfunction "GPIO_SD_B2_08_F15") (pintype "bidirectional"))
    )
    (net (code "65") (name "/FlexSPI_A_D1") (class "Default")
      (node (ref "U5") (pin "H15") (pinfunction "GPIO_SD_B2_09_H15") (pintype "bidirectional"))
    )
    (net (code "66") (name "/FlexSPI_A_D2") (class "Default")
      (node (ref "U5") (pin "H14") (pinfunction "GPIO_SD_B2_10_H14") (pintype "bidirectional"))
    )
    (net (code "67") (name "/FlexSPI_A_D3") (class "Default")
      (node (ref "U5") (pin "F16") (pinfunction "GPIO_SD_B2_11_F16") (pintype "bidirectional"))
    )
    (net (code "68") (name "/FlexSPI_A_SS0") (class "Default")
      (node (ref "U5") (pin "F17") (pinfunction "GPIO_SD_B2_06_F17") (pintype "bidirectional"))
    )
    (net (code "69") (name "/I2C1_SCL_SHTC3") (class "Default")
      (node (ref "U5") (pin "K16") (pinfunction "GPIO_AD_32_K16") (pintype "bidirectional"))
    )
    (net (code "70") (name "/I2C1_SDA_SHTC3") (class "Default")
      (node (ref "U5") (pin "H17") (pinfunction "GPIO_AD_33_H17") (pintype "bidirectional"))
    )
    (net (code "71") (name "/I2C5_SCL") (class "Default")
      (node (ref "R49") (pin "1") (pintype "passive"))
      (node (ref "U10") (pin "5") (pinfunction "2Y_5") (pintype "passive"))
      (node (ref "U13") (pin "5") (pinfunction "2Y_5") (pintype "passive"))
      (node (ref "U5") (pin "N8") (pinfunction "GPIO_LPSR_05_N8") (pintype "bidirectional"))
      (node (ref "U6") (pin "A3") (pinfunction "I2C_SCL_A3") (pintype "passive"))
    )
    (net (code "72") (name "/I2C5_SCL_CAM") (class "Default")
      (node (ref "U13") (pin "6") (pinfunction "2Z_6") (pintype "passive"))
    )
    (net (code "73") (name "/I2C5_SCL_MCM") (class "Default")
      (node (ref "U10") (pin "6") (pinfunction "2Z_6") (pintype "passive"))
    )
    (net (code "74") (name "/I2C5_SDA") (class "Default")
      (node (ref "R48") (pin "1") (pintype "passive"))
      (node (ref "U10") (pin "1") (pinfunction "1Y_1") (pintype "passive"))
      (node (ref "U13") (pin "1") (pinfunction "1Y_1") (pintype "passive"))
      (node (ref "U5") (pin "N7") (pinfunction "GPIO_LPSR_04_N7") (pintype "bidirectional"))
      (node (ref "U6") (pin "A4") (pinfunction "I2C_SDA_A4") (pintype "passive"))
    )
    (net (code "75") (name "/I2C5_SDA_CAM") (class "Default")
      (node (ref "U13") (pin "2") (pinfunction "1Z_2") (pintype "passive"))
    )
    (net (code "76") (name "/I2C5_SDA_MCM") (class "Default")
      (node (ref "U10") (pin "2") (pinfunction "1Z_2") (pintype "passive"))
    )
    (net (code "77") (name "/I2C6_SCL") (class "Default")
      (node (ref "R51") (pin "1") (pintype "passive"))
      (node (ref "U5") (pin "R8") (pinfunction "GPIO_LPSR_07_R8") (pintype "bidirectional"))
    )
    (net (code "78") (name "/I2C6_SDA") (class "Default")
      (node (ref "R50") (pin "1") (pintype "passive"))
      (node (ref "U5") (pin "P8") (pinfunction "GPIO_LPSR_06_P8") (pintype "bidirectional"))
    )
    (net (code "79") (name "/LPSPI1_PCS0_AFE") (class "Default")
      (node (ref "U5") (pin "M17") (pinfunction "GPIO_AD_29_M17") (pintype "bidirectional"))
    )
    (net (code "80") (name "/LPSPI1_SCK_AFE") (class "Default")
      (node (ref "U5") (pin "L17") (pinfunction "GPIO_AD_28_L17") (pintype "bidirectional"))
    )
    (net (code "81") (name "/LPSPI1_SDI_AFE") (class "Default")
      (node (ref "U5") (pin "J17") (pinfunction "GPIO_AD_31_J17") (pintype "bidirectional"))
    )
    (net (code "82") (name "/LPSPI1_SDO_AFE") (class "Default")
      (node (ref "U5") (pin "K17") (pinfunction "GPIO_AD_30_K17") (pintype "bidirectional"))
    )
    (net (code "83") (name "/LPSPI6_CS0") (class "Default")
      (node (ref "U5") (pin "P5") (pinfunction "GPIO_LPSR_09_P5") (pintype "bidirectional"))
    )
    (net (code "84") (name "/LPUART1_RXD") (class "Default")
      (node (ref "U14") (pin "5") (pinfunction "2Y_5") (pintype "passive"))
    )
    (net (code "85") (name "/LPUART1_RXD_BT") (class "Default")
      (node (ref "R21") (pin "1") (pintype "passive"))
      (node (ref "U14") (pin "6") (pinfunction "2Z_6") (pintype "passive"))
      (node (ref "U5") (pin "M15") (pinfunction "GPIO_AD_25_M15") (pintype "bidirectional"))
    )
    (net (code "86") (name "/LPUART1_TXD") (class "Default")
      (node (ref "U14") (pin "1") (pinfunction "1Y_1") (pintype "passive"))
    )
    (net (code "87") (name "/LPUART1_TXD_BT") (class "Default")
      (node (ref "R53") (pin "1") (pintype "passive"))
      (node (ref "U14") (pin "2") (pinfunction "1Z_2") (pintype "passive"))
      (node (ref "U5") (pin "L13") (pinfunction "GPIO_AD_24_L13") (pintype "bidirectional"))
    )
    (net (code "88") (name "/LPUART2_CTS_B") (class "Default")
      (node (ref "R45") (pin "2") (pintype "passive"))
    )
    (net (code "89") (name "/LPUART2_CTS_B_R") (class "Default")
      (node (ref "R45") (pin "1") (pintype "passive"))
      (node (ref "U5") (pin "B6") (pinfunction "GPIO_DISP_B2_12_B6") (pintype "bidirectional"))
    )
    (net (code "90") (name "/LPUART2_RTS_B") (class "Default")
      (node (ref "U5") (pin "A5") (pinfunction "GPIO_DISP_B2_13_A5") (pintype "bidirectional"))
    )
    (net (code "91") (name "/LPUART2_RXD") (class "Default")
      (node (ref "U5") (pin "A6") (pinfunction "GPIO_DISP_B2_11_A6") (pintype "bidirectional"))
    )
    (net (code "92") (name "/LPUART2_TXD") (class "Default")
      (node (ref "U5") (pin "D9") (pinfunction "GPIO_DISP_B2_10_D9") (pintype "bidirectional"))
    )
    (net (code "93") (name "/LPUART8_RXD") (class "Default")
      (node (ref "U5") (pin "D8") (pinfunction "GPIO_DISP_B2_09_D8") (pintype "bidirectional"))
    )
    (net (code "94") (name "/LPUART8_TXD") (class "Default")
      (node (ref "U5") (pin "B5") (pinfunction "GPIO_DISP_B2_08_B5") (pintype "bidirectional"))
    )
    (net (code "95") (name "/MIC_CLK") (class "Default")
      (node (ref "U5") (pin "N6") (pinfunction "GPIO_LPSR_00_N6") (pintype "bidirectional"))
    )
    (net (code "96") (name "/SPI6_SCK__JTAG_nTRST") (class "Default")
      (node (ref "TP18") (pin "1") (pintype "passive"))
      (node (ref "U5") (pin "R5") (pinfunction "GPIO_LPSR_10_R5") (pintype "bidirectional"))
    )
    (net (code "97") (name "/SPI6_SDI__JTAG_TDI") (class "Default")
      (node (ref "TP20") (pin "1") (pintype "passive"))
      (node (ref "U5") (pin "U5") (pinfunction "GPIO_LPSR_12_U5") (pintype "bidirectional"))
    )
    (net (code "98") (name "/SPI6_SDO__JTAG_TDO") (class "Default")
      (node (ref "TP19") (pin "1") (pintype "passive"))
      (node (ref "U5") (pin "T5") (pinfunction "GPIO_LPSR_11_T5") (pintype "bidirectional"))
    )
    (net (code "99") (name "/USB_OTG1_ID") (class "Default") (node (ref "R43") (pin "2") (pintype "passive")))
    (net (code "100") (name "/USB_OTG1_ID_RT") (class "Default")
      (node (ref "R43") (pin "1") (pintype "passive"))
      (node (ref "U5") (pin "R16") (pinfunction "GPIO_AD_09_R16") (pintype "bidirectional"))
    )
    (net (code "101") (name "/USB_PORT_RT") (class "Default")
      (node (ref "U5") (pin "R15") (pinfunction "GPIO_AD_08_R15") (pintype "bidirectional"))
    )
    (net (code "102") (name "/USDHC2_CLK") (class "Default")
      (node (ref "U5") (pin "F14") (pinfunction "GPIO_SD_B2_04_F14") (pintype "bidirectional"))
    )
    (net (code "103") (name "/USDHC2_CMD") (class "Default")
      (node (ref "R23") (pin "1") (pintype "passive"))
      (node (ref "U5") (pin "E14") (pinfunction "GPIO_SD_B2_05_E14") (pintype "bidirectional"))
    )
    (net (code "104") (name "/WIFI_SDIO_CLK") (class "Default")
      (node (ref "U5") (pin "D15") (pinfunction "GPIO_SD_B1_01_D15") (pintype "bidirectional"))
    )
    (net (code "105") (name "/WIFI_SDIO_CMD") (class "Default")
      (node (ref "R32") (pin "2") (pintype "passive"))
    )
    (net (code "106") (name "/WIFI_SDIO_CMD_R") (class "Default")
      (node (ref "R32") (pin "1") (pintype "passive"))
      (node (ref "R373") (pin "1") (pintype "passive"))
      (node (ref "U5") (pin "B16") (pinfunction "GPIO_SD_B1_00_B16") (pintype "bidirectional"))
    )
    (net (code "107") (name "/WIFI_SDIO_D0") (class "Default")
      (node (ref "R33") (pin "2") (pintype "passive"))
    )
    (net (code "108") (name "/WIFI_SDIO_D0_R") (class "Default")
      (node (ref "R33") (pin "1") (pintype "passive"))
      (node (ref "R374") (pin "1") (pintype "passive"))
      (node (ref "U5") (pin "C15") (pinfunction "GPIO_SD_B1_02_C15") (pintype "bidirectional"))
    )
    (net (code "109") (name "/WIFI_SDIO_D1") (class "Default")
      (node (ref "R34") (pin "2") (pintype "passive"))
    )
    (net (code "110") (name "/WIFI_SDIO_D1_R") (class "Default")
      (node (ref "R34") (pin "1") (pintype "passive"))
      (node (ref "U5") (pin "B17") (pinfunction "GPIO_SD_B1_03_B17") (pintype "bidirectional"))
    )
    (net (code "111") (name "/WIFI_SDIO_D2") (class "Default")
      (node (ref "R35") (pin "2") (pintype "passive"))
    )
    (net (code "112") (name "/WIFI_SDIO_D2_R") (class "Default")
      (node (ref "R35") (pin "1") (pintype "passive"))
      (node (ref "U5") (pin "B15") (pinfunction "GPIO_SD_B1_04_B15") (pintype "bidirectional"))
    )
    (net (code "113") (name "/WIFI_SDIO_D3") (class "Default")
      (node (ref "R36") (pin "2") (pintype "passive"))
    )
    (net (code "114") (name "/WIFI_SDIO_D3_R") (class "Default")
      (node (ref "R36") (pin "1") (pintype "passive"))
      (node (ref "U5") (pin "A16") (pinfunction "GPIO_SD_B1_05_A16") (pintype "bidirectional"))
    )
    (net (code "115") (name "/WL_ANT_SEL") (class "Default")
      (node (ref "U5") (pin "C6") (pinfunction "GPIO_DISP_B2_06_C6") (pintype "bidirectional"))
    )
    (net (code "116") (name "/WL_HOST_WAKE") (class "Default")
      (node (ref "U5") (pin "D6") (pinfunction "GPIO_DISP_B2_07_D6") (pintype "bidirectional"))
    )
    (net (code "117") (name "/WL_REG_ON") (class "Default")
      (node (ref "U5") (pin "J16") (pinfunction "GPIO_AD_34_J16") (pintype "bidirectional"))
    )
    (net (code "118") (name "DCDC_1V8_OUT") (class "Default")
      (node (ref "R23") (pin "2") (pintype "passive"))
      (node (ref "R24") (pin "2") (pintype "passive"))
      (node (ref "R373") (pin "2") (pintype "passive"))
      (node (ref "R374") (pin "2") (pintype "passive"))
    )
    (net (code "119") (name "GND") (class "Default")
      (node (ref "C242") (pin "2") (pintype "passive"))
      (node (ref "C254") (pin "2") (pintype "passive"))
      (node (ref "C256") (pin "2") (pintype "passive"))
      (node (ref "C258") (pin "2") (pintype "passive"))
      (node (ref "C285") (pin "2") (pintype "passive"))
      (node (ref "C327") (pin "2") (pintype "passive"))
      (node (ref "C33") (pin "2") (pintype "passive"))
      (node (ref "C345") (pin "2") (pintype "passive"))
      (node (ref "R27") (pin "1") (pintype "passive"))
      (node (ref "R38") (pin "1") (pintype "passive"))
      (node (ref "R41") (pin "1") (pintype "passive"))
      (node (ref "U10") (pin "4") (pinfunction "GND_4") (pintype "passive"))
      (node (ref "U13") (pin "4") (pinfunction "GND_4") (pintype "passive"))
      (node (ref "U14") (pin "4") (pinfunction "GND_4") (pintype "passive"))
      (node (ref "U6") (pin "A1") (pinfunction "NC_A1") (pintype "passive"))
      (node (ref "U6") (pin "A2") (pinfunction "VSS_A2") (pintype "power_in"))
      (node (ref "U6") (pin "C2") (pinfunction "IC_C2") (pintype "passive"))
    )
    (net (code "120") (name "MCM_1V8") (class "Default")
      (node (ref "U10") (pin "3") (pinfunction "2E_3") (pintype "passive"))
      (node (ref "U10") (pin "7") (pinfunction "1E_7") (pintype "passive"))
    )
    (net (code "121") (name "Net-(U5G-NVCC_SD1)") (class "Default")
      (node (ref "C242") (pin "1") (pintype "passive"))
      (node (ref "R375") (pin "2") (pintype "passive"))
      (node (ref "U5") (pin "D14") (pinfunction "NVCC_SD1_D14") (pintype "power_in"))
    )
    (net (code "122") (name "VDD_1V8") (class "Default")
      (node (ref "C254") (pin "1") (pintype "passive"))
      (node (ref "C256") (pin "1") (pintype "passive"))
      (node (ref "C258") (pin "1") (pintype "passive"))
      (node (ref "C285") (pin "1") (pintype "passive"))
      (node (ref "C327") (pin "1") (pintype "passive"))
      (node (ref "C345") (pin "1") (pintype "passive"))
      (node (ref "R21") (pin "2") (pintype "passive"))
      (node (ref "R37") (pin "2") (pintype "passive"))
      (node (ref "R375") (pin "1") (pintype "passive"))
      (node (ref "R48") (pin "2") (pintype "passive"))
      (node (ref "R49") (pin "2") (pintype "passive"))
      (node (ref "R50") (pin "2") (pintype "passive"))
      (node (ref "R51") (pin "2") (pintype "passive"))
      (node (ref "R53") (pin "2") (pintype "passive"))
      (node (ref "U10") (pin "8") (pinfunction "VCC_8") (pintype "passive"))
      (node (ref "U13") (pin "8") (pinfunction "VCC_8") (pintype "passive"))
      (node (ref "U14") (pin "8") (pinfunction "VCC_8") (pintype "passive"))
      (node (ref "U5") (pin "D12") (pinfunction "NVCC_DISP1_D12") (pintype "passive"))
      (node (ref "U5") (pin "E7") (pinfunction "NVCC_DISP2_E7") (pintype "passive"))
      (node (ref "U5") (pin "G13") (pinfunction "NVCC_SD2_G13") (pintype "power_in"))
      (node (ref "U5") (pin "M12") (pinfunction "NVCC_GPIO_M12") (pintype "power_in"))
      (node (ref "U5") (pin "P7") (pinfunction "NVCC_LPSR_P7") (pintype "passive"))
      (node (ref "U6") (pin "B2") (pinfunction "VCC_B2") (pintype "power_in"))
      (node (ref "U6") (pin "B3") (pinfunction "NC_B3") (pintype "passive"))
      (node (ref "U6") (pin "B4") (pinfunction "IF1_B4") (pintype "passive"))
      (node (ref "U6") (pin "C4") (pinfunction "IF0_C4") (pintype "passive"))
    )
    (net (code "123") (name "VDD_1V8_CAM") (class "Default")
      (node (ref "U13") (pin "3") (pinfunction "2E_3") (pintype "passive"))
      (node (ref "U13") (pin "7") (pinfunction "1E_7") (pintype "passive"))
    )
    (net (code "124") (name "VSYS") (class "Default") (node (ref "R40") (pin "2") (pintype "passive")))
    (net (code "125") (name "unconnected-(U5H-GPIO_AD_04-PadM13)") (class "Default")
      (node (ref "U5") (pin "M13") (pinfunction "GPIO_AD_04_M13") (pintype "bidirectional+no_connect"))
    )
    (net (code "126") (name "unconnected-(U6-NC-PadB1)") (class "Default")
      (node (ref "U6") (pin "B1") (pinfunction "NC_B1") (pintype "passive+no_connect"))
    )
    (net (code "127") (name "unconnected-(U6-NC-PadC1)") (class "Default")
      (node (ref "U6") (pin "C1") (pinfunction "NC_C1") (pintype "passive+no_connect"))
    )
  )
)
